# USB.net
KiCad netlist of a schematic drawn in Altium Designer
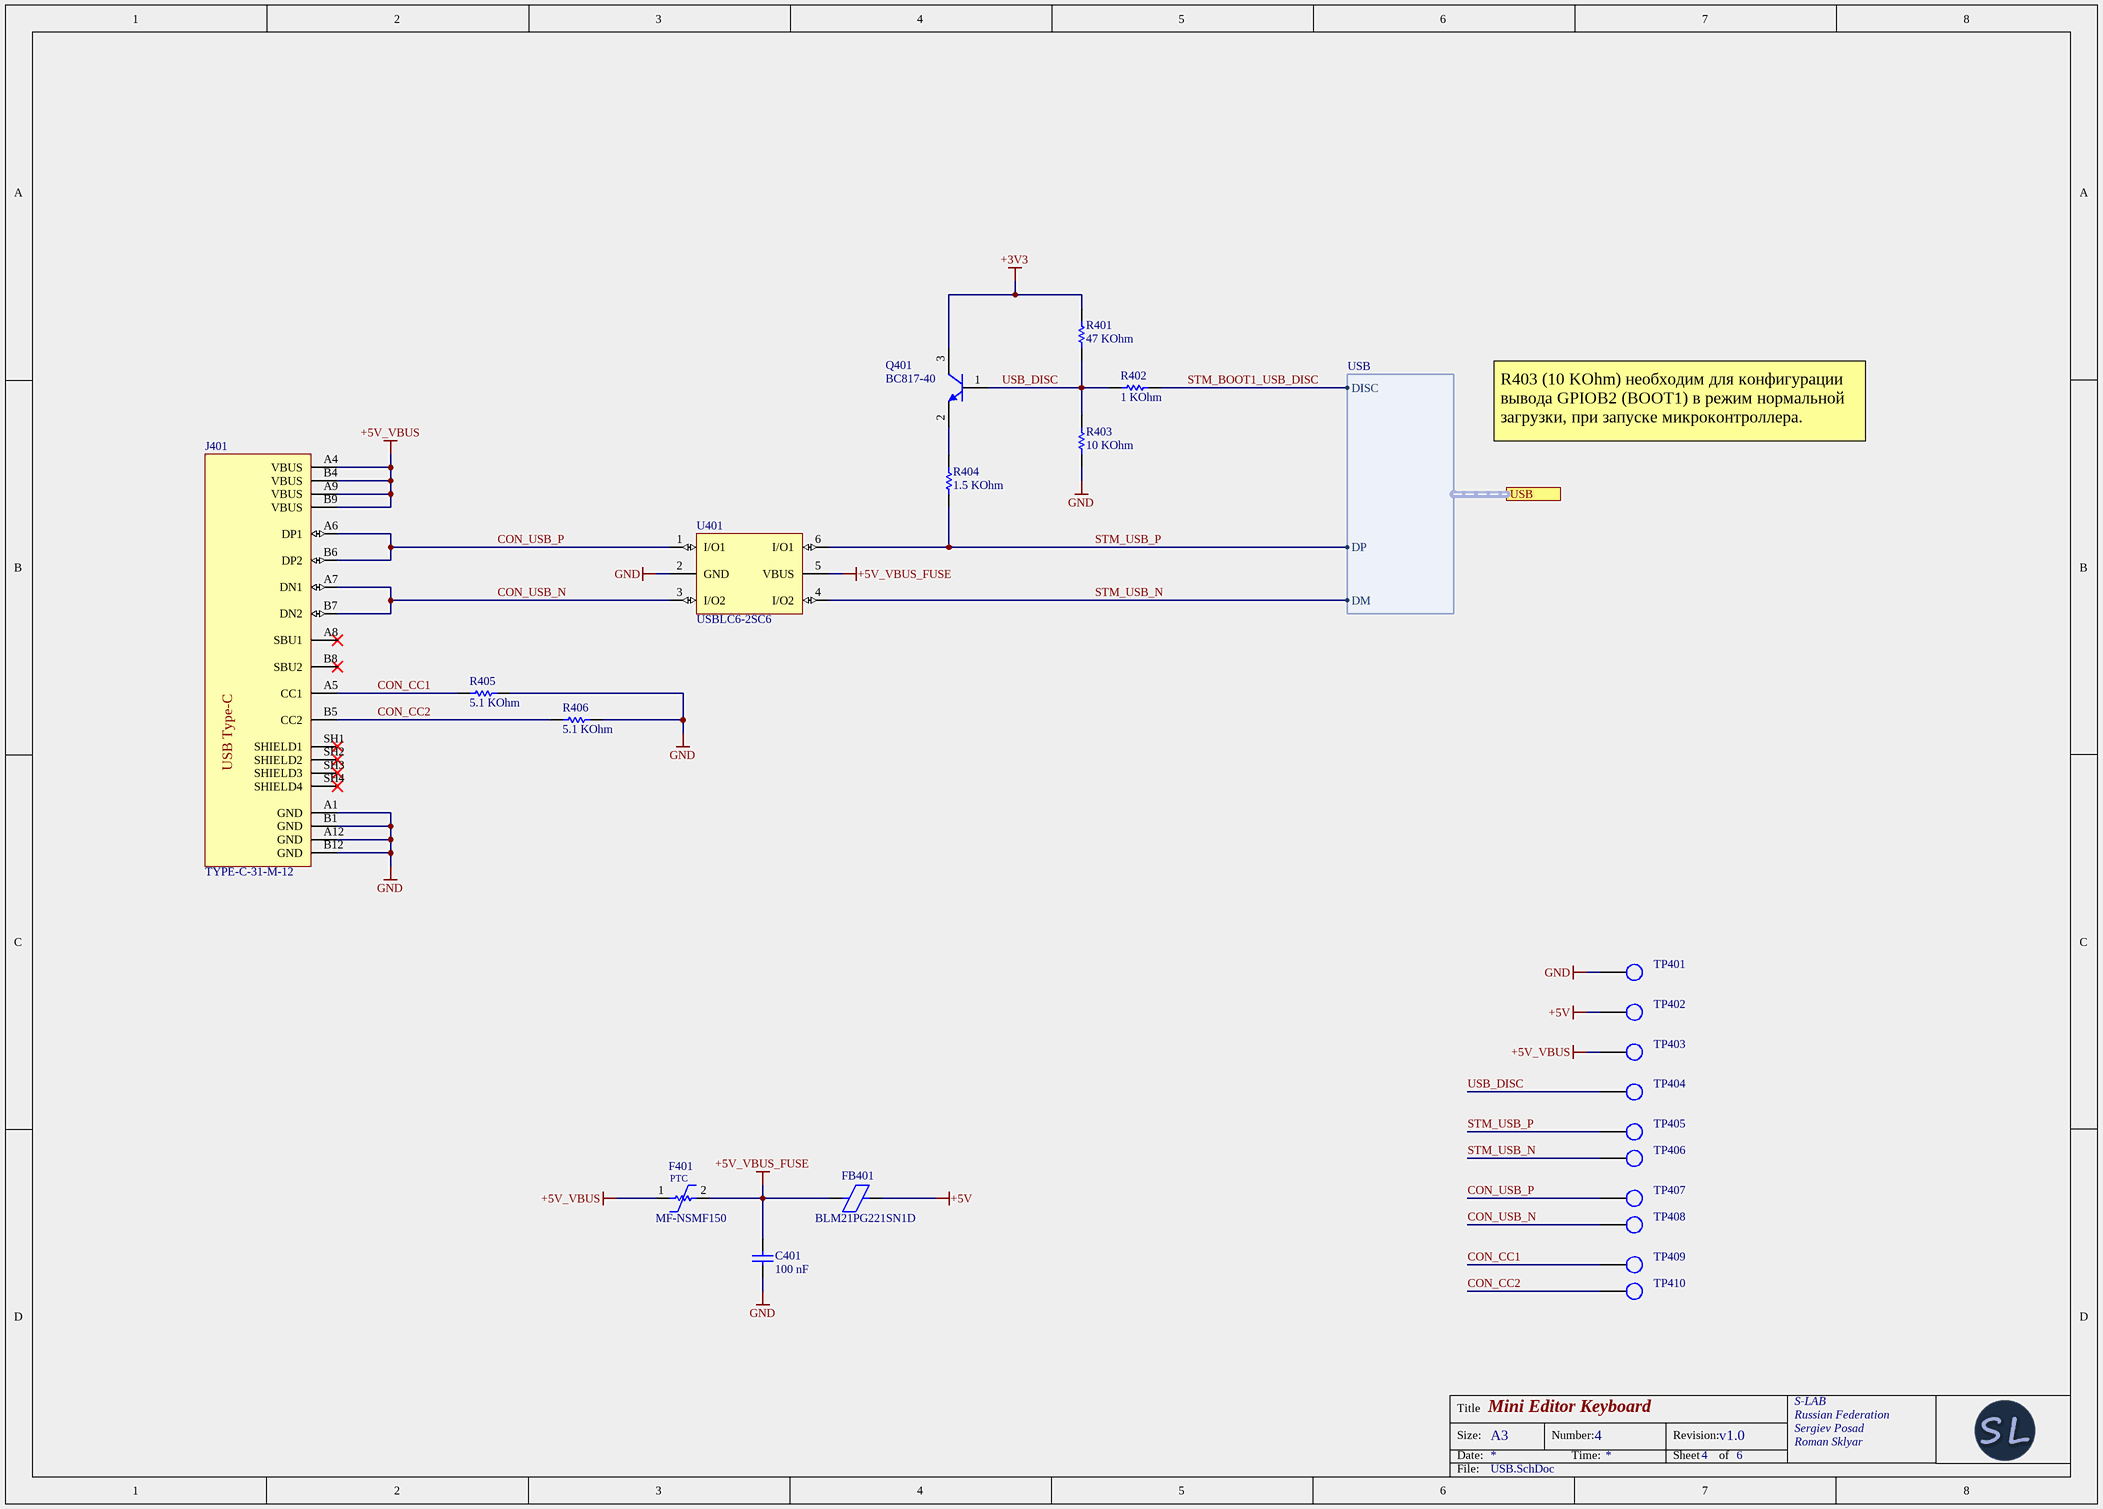
[diagram p0: USB.SchDoc]

(export (version "E")
  (design (tool "Eeschema 10.0.6"))
  (components
    (comp (ref "C401")
      (value "CAP-100N")
      (footprint "CAPC0603")
      (description "Chip Capacitor, 100 nF, +/- 5%")
      (fields (field (name "TOLERANCE") "5 %") (field (name "CAPACITANCE") "100 nF"))
      (libsource (lib "Конденсаторы керамические SMD") (part "CAP-100N"))
    )
    (comp (ref "F401")
      (value "MF-NSMF150")
      (footprint "PTC1206-BOURNS")
      (description "PTC Resettable Fuses 6V 1.5A")
      (fields (field (name "PARTNUMBER") "MF-NSMF150"))
      (libsource (lib "Предохранители") (part "MF-NSMF150"))
    )
    (comp (ref "FB401")
      (value "BLM21PG221SN1D")
      (footprint "INDC-0805-2012X10")
      (description "220Ω @ 100MHz 2A 45mΩ 0805 Ferrite Beads")
      (fields (field (name "PARTNUMBER") "BLM21PG221SN1D"))
      (libsource (lib "Ферритовые катушки") (part "BLM21PG221SN1D"))
    )
    (comp (ref "J401")
      (value "TYPE-C-31-M-12")
      (footprint "TYPE-C-31-M-12")
      (description "USB - Type C Female 16 8.94*7.3mm USB Connectors")
      (fields (field (name "PARTNUMBER") "TYPE-C-31-M-12"))
      (libsource (lib "Разъемы") (part "TYPE-C-31-M-12"))
    )
    (comp (ref "Q401")
      (value "BC817-40")
      (footprint "SOT23-3-AnBon")
      (description "NPN 500mA 45V 300mW SOT-23, hFE 250-600")
      (fields (field (name "PARTNUMBER") "BC817-40"))
      (libsource (lib "Транзисторы биполярные") (part "BC817-40"))
    )
    (comp (ref "R401")
      (value "RES-47K")
      (footprint "RES0603")
      (description "Chip Resistor, 47 KOhm, +/- 1%")
      (fields (field (name "TOLERANCE") "1 %") (field (name "RESISTANCE") "47 KOhm"))
      (libsource (lib "Резисторы SMD") (part "RES-47K"))
    )
    (comp (ref "R402")
      (value "RES-1K")
      (footprint "RES0603")
      (description "Chip Resistor, 1 KOhm, +/- 1%")
      (fields (field (name "TOLERANCE") "1 %") (field (name "RESISTANCE") "1 KOhm"))
      (libsource (lib "Резисторы SMD") (part "RES-1K"))
    )
    (comp (ref "R403")
      (value "RES-10K")
      (footprint "RES0603")
      (description "Chip Resistor, 10 KOhm, +/- 1%")
      (fields (field (name "TOLERANCE") "1 %") (field (name "RESISTANCE") "10 KOhm"))
      (libsource (lib "Резисторы SMD") (part "RES-10K"))
    )
    (comp (ref "R404")
      (value "RES-1K5")
      (footprint "RES0603")
      (description "Chip Resistor, 1.5 KOhm, +/- 1%")
      (fields (field (name "TOLERANCE") "1 %") (field (name "RESISTANCE") "1.5 KOhm"))
      (libsource (lib "Резисторы SMD") (part "RES-1K5"))
    )
    (comp (ref "R405")
      (value "RES-5K1")
      (footprint "RES0603")
      (description "Chip Resistor, 5.1 KOhm, +/- 1%")
      (fields (field (name "TOLERANCE") "1 %") (field (name "RESISTANCE") "5.1 KOhm"))
      (libsource (lib "Резисторы SMD") (part "RES-5K1"))
    )
    (comp (ref "R406")
      (value "RES-5K1")
      (footprint "RES0603")
      (description "Chip Resistor, 5.1 KOhm, +/- 1%")
      (fields (field (name "TOLERANCE") "1 %") (field (name "RESISTANCE") "5.1 KOhm"))
      (libsource (lib "Резисторы SMD") (part "RES-5K1"))
    )
    (comp (ref "TP401") (value "~") (footprint "TP_C-0.5mm") (libsource (lib "Разъемы") (part "TestPad")))
    (comp (ref "TP402") (value "~") (footprint "TP_C-0.5mm") (libsource (lib "Разъемы") (part "TestPad")))
    (comp (ref "TP403") (value "~") (footprint "TP_C-0.5mm") (libsource (lib "Разъемы") (part "TestPad")))
    (comp (ref "TP404") (value "~") (footprint "TP_C-0.5mm") (libsource (lib "Разъемы") (part "TestPad")))
    (comp (ref "TP405") (value "~") (footprint "TP_C-0.5mm") (libsource (lib "Разъемы") (part "TestPad")))
    (comp (ref "TP406") (value "~") (footprint "TP_C-0.5mm") (libsource (lib "Разъемы") (part "TestPad")))
    (comp (ref "TP407") (value "~") (footprint "TP_C-0.5mm") (libsource (lib "Разъемы") (part "TestPad")))
    (comp (ref "TP408") (value "~") (footprint "TP_C-0.5mm") (libsource (lib "Разъемы") (part "TestPad")))
    (comp (ref "TP409") (value "~") (footprint "TP_C-0.5mm") (libsource (lib "Разъемы") (part "TestPad")))
    (comp (ref "TP410") (value "~") (footprint "TP_C-0.5mm") (libsource (lib "Разъемы") (part "TestPad")))
    (comp (ref "U401")
      (value "USBLC6-2SC6")
      (footprint "SOT23-6L-STM")
      (description "Very low capacitance ESD protection  3.5 pF max")
      (fields (field (name "PARTNUMBER") "USBLC6-2SC6"))
      (libsource (lib "Диоды TVS") (part "USBLC6-2SC6"))
    )
  )
  (nets
    (net (code "2") (name "+3V3") (class "Default")
      (node (ref "Q401") (pin "3") (pinfunction "C_3") (pintype "passive"))
      (node (ref "R401") (pin "2") (pinfunction "2_2") (pintype "passive"))
    )
    (net (code "3") (name "+5V") (class "Default")
      (node (ref "FB401") (pin "2") (pinfunction "2_2") (pintype "passive"))
      (node (ref "TP402") (pin "1") (pintype "passive"))
    )
    (net (code "4") (name "+5V_VBUS") (class "Default")
      (node (ref "F401") (pin "1") (pinfunction "1_1") (pintype "passive"))
      (node (ref "J401") (pin "A4") (pinfunction "VBUS_A4") (pintype "power_in"))
      (node (ref "J401") (pin "A9") (pinfunction "VBUS_A9") (pintype "power_in"))
      (node (ref "J401") (pin "B4") (pinfunction "VBUS_B4") (pintype "power_in"))
      (node (ref "J401") (pin "B9") (pinfunction "VBUS_B9") (pintype "power_in"))
      (node (ref "TP403") (pin "1") (pintype "passive"))
    )
    (net (code "5") (name "+5V_VBUS_FUSE") (class "Default")
      (node (ref "C401") (pin "2") (pinfunction "2_2") (pintype "passive"))
      (node (ref "F401") (pin "2") (pinfunction "2_2") (pintype "passive"))
      (node (ref "FB401") (pin "1") (pinfunction "1_1") (pintype "passive"))
      (node (ref "U401") (pin "5") (pinfunction "VBUS_5") (pintype "power_in"))
    )
    (net (code "6") (name "/CON_CC1") (class "Default")
      (node (ref "J401") (pin "A5") (pinfunction "CC1_A5") (pintype "passive"))
      (node (ref "R405") (pin "2") (pinfunction "2_2") (pintype "passive"))
      (node (ref "TP409") (pin "1") (pintype "passive"))
    )
    (net (code "7") (name "/CON_CC2") (class "Default")
      (node (ref "J401") (pin "B5") (pinfunction "CC2_B5") (pintype "passive"))
      (node (ref "R406") (pin "2") (pinfunction "2_2") (pintype "passive"))
      (node (ref "TP410") (pin "1") (pintype "passive"))
    )
    (net (code "8") (name "/CON_USB_N") (class "Default")
      (node (ref "J401") (pin "A7") (pinfunction "DN1_A7") (pintype "bidirectional"))
      (node (ref "J401") (pin "B7") (pinfunction "DN2_B7") (pintype "bidirectional"))
      (node (ref "TP408") (pin "1") (pintype "passive"))
      (node (ref "U401") (pin "3") (pinfunction "I/O2_3") (pintype "bidirectional"))
    )
    (net (code "9") (name "/CON_USB_P") (class "Default")
      (node (ref "J401") (pin "A6") (pinfunction "DP1_A6") (pintype "bidirectional"))
      (node (ref "J401") (pin "B6") (pinfunction "DP2_B6") (pintype "bidirectional"))
      (node (ref "TP407") (pin "1") (pintype "passive"))
      (node (ref "U401") (pin "1") (pinfunction "I/O1_1") (pintype "bidirectional"))
    )
    (net (code "10") (name "/STM_BOOT1_USB_DISC") (class "Default")
      (node (ref "R402") (pin "2") (pinfunction "2_2") (pintype "passive"))
    )
    (net (code "11") (name "/STM_USB_N") (class "Default")
      (node (ref "TP406") (pin "1") (pintype "passive"))
      (node (ref "U401") (pin "4") (pinfunction "I/O2_4") (pintype "bidirectional"))
    )
    (net (code "12") (name "/STM_USB_P") (class "Default")
      (node (ref "R404") (pin "2") (pinfunction "2_2") (pintype "passive"))
      (node (ref "TP405") (pin "1") (pintype "passive"))
      (node (ref "U401") (pin "6") (pinfunction "I/O1_6") (pintype "bidirectional"))
    )
    (net (code "13") (name "/USB_DISC") (class "Default")
      (node (ref "Q401") (pin "1") (pinfunction "B_1") (pintype "passive"))
      (node (ref "R401") (pin "1") (pinfunction "1_1") (pintype "passive"))
      (node (ref "R402") (pin "1") (pinfunction "1_1") (pintype "passive"))
      (node (ref "R403") (pin "2") (pinfunction "2_2") (pintype "passive"))
      (node (ref "TP404") (pin "1") (pintype "passive"))
    )
    (net (code "15") (name "GND") (class "Default")
      (node (ref "C401") (pin "1") (pinfunction "1_1") (pintype "passive"))
      (node (ref "J401") (pin "A1") (pinfunction "GND_A1") (pintype "power_in"))
      (node (ref "J401") (pin "A12") (pinfunction "GND_A12") (pintype "power_in"))
      (node (ref "J401") (pin "B1") (pinfunction "GND_B1") (pintype "power_in"))
      (node (ref "J401") (pin "B12") (pinfunction "GND_B12") (pintype "power_in"))
      (node (ref "R403") (pin "1") (pinfunction "1_1") (pintype "passive"))
      (node (ref "R405") (pin "1") (pinfunction "1_1") (pintype "passive"))
      (node (ref "R406") (pin "1") (pinfunction "1_1") (pintype "passive"))
      (node (ref "TP401") (pin "1") (pintype "passive"))
      (node (ref "U401") (pin "2") (pinfunction "GND_2") (pintype "power_in"))
    )
    (net (code "16") (name "Net-(Q401-E)") (class "Default")
      (node (ref "Q401") (pin "2") (pinfunction "E_2") (pintype "passive"))
      (node (ref "R404") (pin "1") (pinfunction "1_1") (pintype "passive"))
    )
    (net (code "17") (name "unconnected-(J401-SBU1-PadA8)") (class "Default")
      (node (ref "J401") (pin "A8") (pinfunction "SBU1_A8") (pintype "passive+no_connect"))
    )
    (net (code "18") (name "unconnected-(J401-SBU2-PadB8)") (class "Default")
      (node (ref "J401") (pin "B8") (pinfunction "SBU2_B8") (pintype "passive+no_connect"))
    )
    (net (code "19") (name "unconnected-(J401-SHIELD1-PadSH1)") (class "Default")
      (node (ref "J401") (pin "SH1") (pinfunction "SHIELD1_SH1") (pintype "power_in+no_connect"))
    )
    (net (code "20") (name "unconnected-(J401-SHIELD2-PadSH2)") (class "Default")
      (node (ref "J401") (pin "SH2") (pinfunction "SHIELD2_SH2") (pintype "power_in+no_connect"))
    )
    (net (code "21") (name "unconnected-(J401-SHIELD3-PadSH3)") (class "Default")
      (node (ref "J401") (pin "SH3") (pinfunction "SHIELD3_SH3") (pintype "power_in+no_connect"))
    )
    (net (code "22") (name "unconnected-(J401-SHIELD4-PadSH4)") (class "Default")
      (node (ref "J401") (pin "SH4") (pinfunction "SHIELD4_SH4") (pintype "power_in+no_connect"))
    )
  )
)
